# TouScruino-ui2_IL-v0.net
KiCad netlist of a schematic drawn in EAGLE
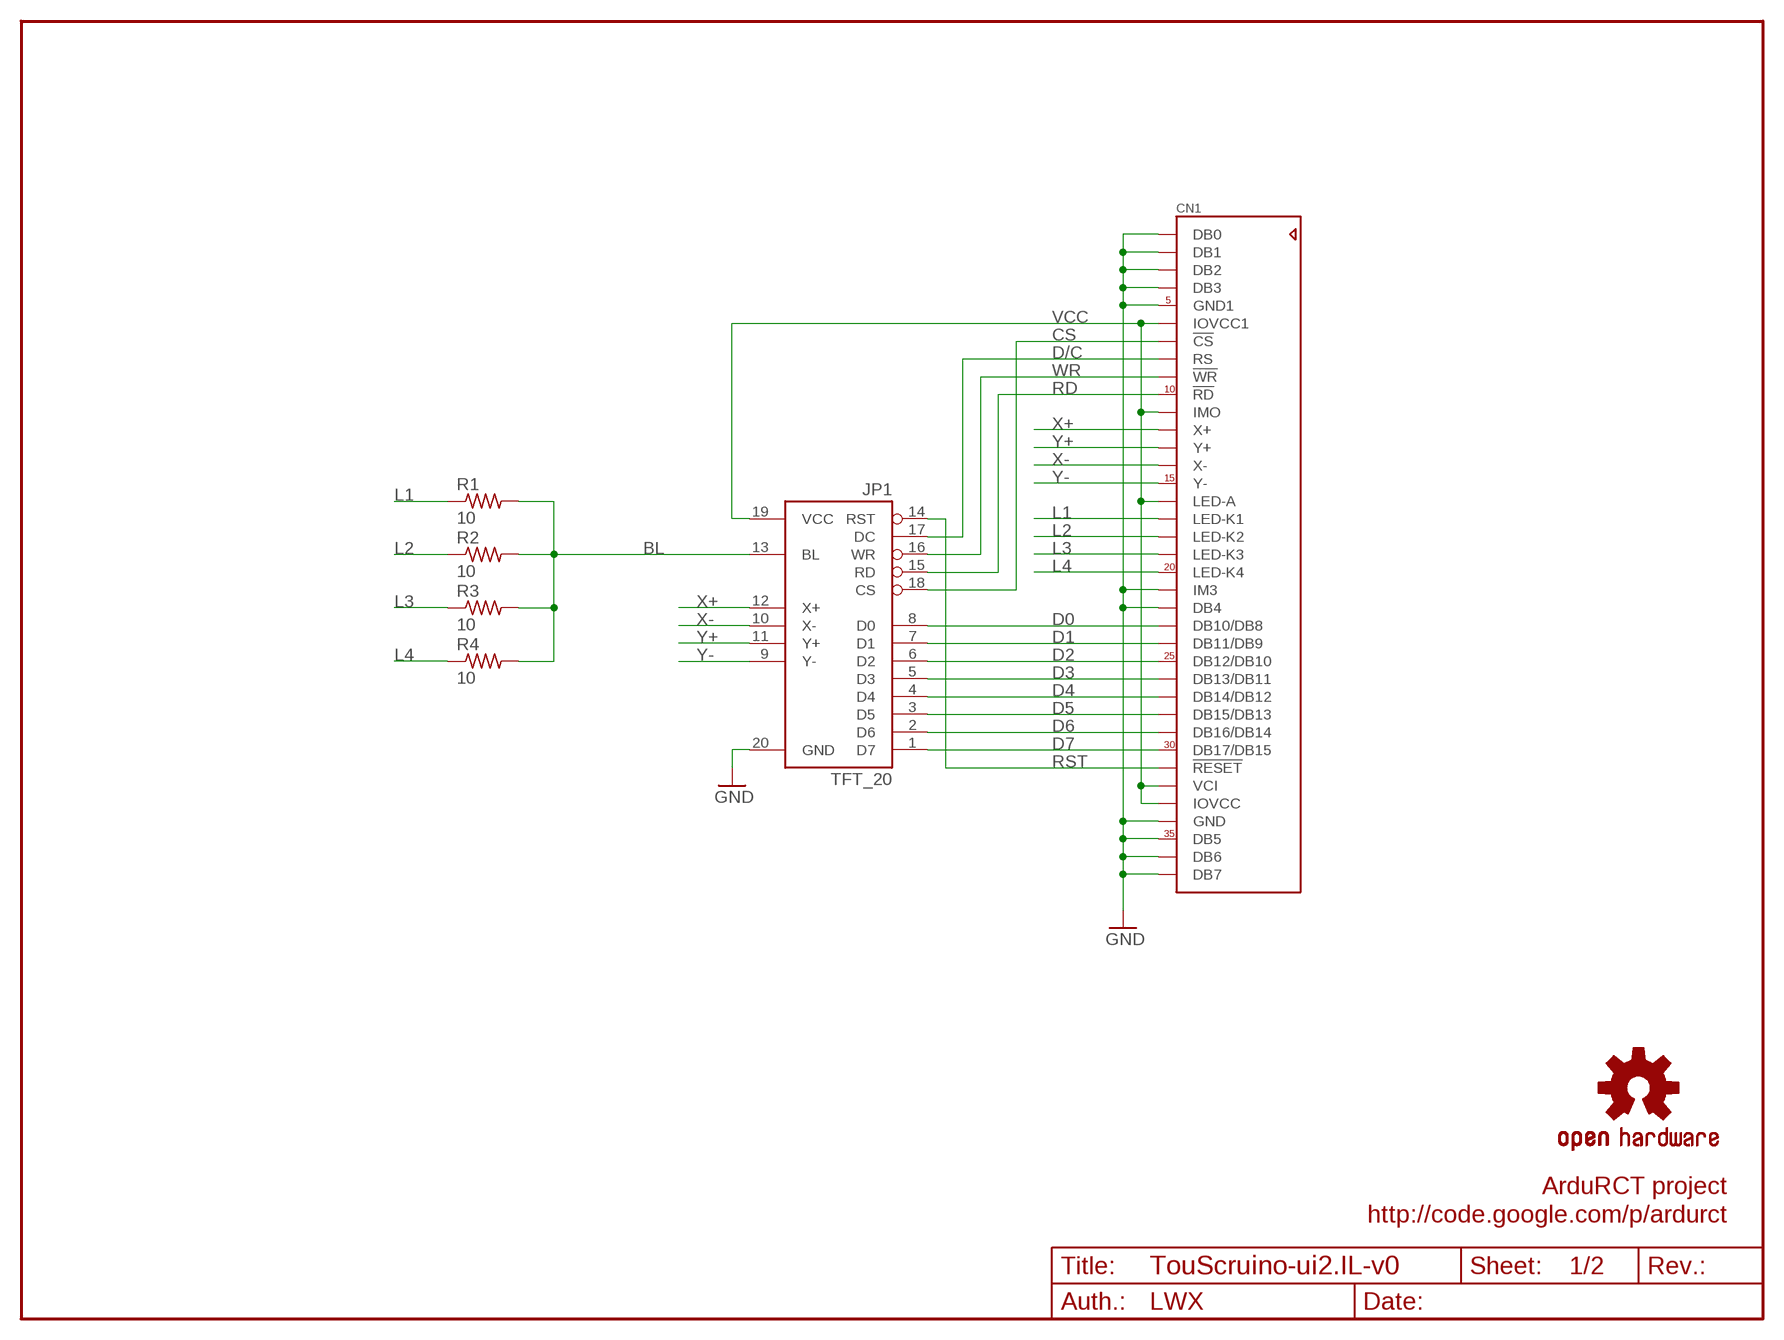
[diagram p0: schematic, sheet 1]

(export (version "E")
  (design (tool "Eeschema 10.0.6"))
  (components
    (comp (ref "CN1")
      (value "ILI9325_LCD1.0MM")
      (footprint "eagle-import:ILI9325_28INCH_TS")
      (libsource (lib "eagle-import") (part "ILI9325_LCD1.0MM"))
    )
    (comp (ref "JP1")
      (value "TFT_20")
      (footprint "eagle-import:TFT_20")
      (libsource (lib "eagle-import") (part "TFT_20"))
    )
    (comp (ref "R1")
      (value "10")
      (footprint "eagle-import:R0603")
      (libsource (lib "eagle-import") (part "R-US_R0603"))
    )
    (comp (ref "R2")
      (value "10")
      (footprint "eagle-import:R0603")
      (libsource (lib "eagle-import") (part "R-US_R0603"))
    )
    (comp (ref "R3")
      (value "10")
      (footprint "eagle-import:R0603")
      (libsource (lib "eagle-import") (part "R-US_R0603"))
    )
    (comp (ref "R4")
      (value "10")
      (footprint "eagle-import:R0603")
      (libsource (lib "eagle-import") (part "R-US_R0603"))
    )
    (comp (ref "U$3")
      (value "OSHW-LOGOM")
      (footprint "eagle-import:OSHW-LOGO-M")
      (libsource (lib "eagle-import") (part "OSHW-LOGOM"))
    )
  )
  (nets
    (net (code "1") (name "/BL") (class "Default")
      (node (ref "JP1") (pin "13") (pinfunction "BL_13") (pintype "bidirectional"))
      (node (ref "R1") (pin "2") (pinfunction "2_2") (pintype "passive"))
      (node (ref "R2") (pin "2") (pinfunction "2_2") (pintype "passive"))
      (node (ref "R3") (pin "2") (pinfunction "2_2") (pintype "passive"))
      (node (ref "R4") (pin "2") (pinfunction "2_2") (pintype "passive"))
    )
    (net (code "2") (name "/CS") (class "Default")
      (node (ref "CN1") (pin "7") (pinfunction "~{CS}_7") (pintype "passive"))
      (node (ref "JP1") (pin "18") (pinfunction "CS_18") (pintype "bidirectional"))
    )
    (net (code "3") (name "/D0") (class "Default")
      (node (ref "CN1") (pin "23") (pinfunction "DB10/DB8_23") (pintype "passive"))
      (node (ref "JP1") (pin "8") (pinfunction "D0_8") (pintype "bidirectional"))
    )
    (net (code "4") (name "/D1") (class "Default")
      (node (ref "CN1") (pin "24") (pinfunction "DB11/DB9_24") (pintype "passive"))
      (node (ref "JP1") (pin "7") (pinfunction "D1_7") (pintype "bidirectional"))
    )
    (net (code "5") (name "/D2") (class "Default")
      (node (ref "CN1") (pin "25") (pinfunction "DB12/DB10_25") (pintype "passive"))
      (node (ref "JP1") (pin "6") (pinfunction "D2_6") (pintype "bidirectional"))
    )
    (net (code "6") (name "/D3") (class "Default")
      (node (ref "CN1") (pin "26") (pinfunction "DB13/DB11_26") (pintype "passive"))
      (node (ref "JP1") (pin "5") (pinfunction "D3_5") (pintype "bidirectional"))
    )
    (net (code "7") (name "/D4") (class "Default")
      (node (ref "CN1") (pin "27") (pinfunction "DB14/DB12_27") (pintype "passive"))
      (node (ref "JP1") (pin "4") (pinfunction "D4_4") (pintype "bidirectional"))
    )
    (net (code "8") (name "/D5") (class "Default")
      (node (ref "CN1") (pin "28") (pinfunction "DB15/DB13_28") (pintype "passive"))
      (node (ref "JP1") (pin "3") (pinfunction "D5_3") (pintype "bidirectional"))
    )
    (net (code "9") (name "/D6") (class "Default")
      (node (ref "CN1") (pin "29") (pinfunction "DB16/DB14_29") (pintype "passive"))
      (node (ref "JP1") (pin "2") (pinfunction "D6_2") (pintype "bidirectional"))
    )
    (net (code "10") (name "/D7") (class "Default")
      (node (ref "CN1") (pin "30") (pinfunction "DB17/DB15_30") (pintype "passive"))
      (node (ref "JP1") (pin "1") (pinfunction "D7_1") (pintype "bidirectional"))
    )
    (net (code "11") (name "/D{slash}C") (class "Default")
      (node (ref "CN1") (pin "8") (pinfunction "RS_8") (pintype "passive"))
      (node (ref "JP1") (pin "17") (pinfunction "DC_17") (pintype "bidirectional"))
    )
    (net (code "12") (name "/L1") (class "Default")
      (node (ref "CN1") (pin "17") (pinfunction "LED-K1_17") (pintype "passive"))
      (node (ref "R1") (pin "1") (pinfunction "1_1") (pintype "passive"))
    )
    (net (code "13") (name "/L2") (class "Default")
      (node (ref "CN1") (pin "18") (pinfunction "LED-K2_18") (pintype "passive"))
      (node (ref "R2") (pin "1") (pinfunction "1_1") (pintype "passive"))
    )
    (net (code "14") (name "/L3") (class "Default")
      (node (ref "CN1") (pin "19") (pinfunction "LED-K3_19") (pintype "passive"))
      (node (ref "R3") (pin "1") (pinfunction "1_1") (pintype "passive"))
    )
    (net (code "15") (name "/L4") (class "Default")
      (node (ref "CN1") (pin "20") (pinfunction "LED-K4_20") (pintype "passive"))
      (node (ref "R4") (pin "1") (pinfunction "1_1") (pintype "passive"))
    )
    (net (code "16") (name "/RD") (class "Default")
      (node (ref "CN1") (pin "10") (pinfunction "~{RD}_10") (pintype "passive"))
      (node (ref "JP1") (pin "15") (pinfunction "RD_15") (pintype "bidirectional"))
    )
    (net (code "17") (name "/RST") (class "Default")
      (node (ref "CN1") (pin "31") (pinfunction "~{RESET}_31") (pintype "passive"))
      (node (ref "JP1") (pin "14") (pinfunction "RST_14") (pintype "bidirectional"))
    )
    (net (code "18") (name "/VCC") (class "Default")
      (node (ref "CN1") (pin "11") (pinfunction "IMO_11") (pintype "passive"))
      (node (ref "CN1") (pin "16") (pinfunction "LED-A_16") (pintype "passive"))
      (node (ref "CN1") (pin "32") (pinfunction "VCI_32") (pintype "power_in"))
      (node (ref "CN1") (pin "33") (pinfunction "IOVCC_33") (pintype "power_in"))
      (node (ref "CN1") (pin "6") (pinfunction "IOVCC1_6") (pintype "power_in"))
      (node (ref "JP1") (pin "19") (pinfunction "VCC_19") (pintype "bidirectional"))
    )
    (net (code "19") (name "/WR") (class "Default")
      (node (ref "CN1") (pin "9") (pinfunction "~{WR}_9") (pintype "passive"))
      (node (ref "JP1") (pin "16") (pinfunction "WR_16") (pintype "bidirectional"))
    )
    (net (code "20") (name "/X+") (class "Default")
      (node (ref "CN1") (pin "12") (pinfunction "X+_12") (pintype "passive"))
      (node (ref "JP1") (pin "12") (pinfunction "X+_12") (pintype "bidirectional"))
    )
    (net (code "21") (name "/X-") (class "Default")
      (node (ref "CN1") (pin "14") (pinfunction "X-_14") (pintype "passive"))
      (node (ref "JP1") (pin "10") (pinfunction "X-_10") (pintype "bidirectional"))
    )
    (net (code "22") (name "/Y+") (class "Default")
      (node (ref "CN1") (pin "13") (pinfunction "Y+_13") (pintype "passive"))
      (node (ref "JP1") (pin "11") (pinfunction "Y+_11") (pintype "bidirectional"))
    )
    (net (code "23") (name "/Y-") (class "Default")
      (node (ref "CN1") (pin "15") (pinfunction "Y-_15") (pintype "passive"))
      (node (ref "JP1") (pin "9") (pinfunction "Y-_9") (pintype "bidirectional"))
    )
    (net (code "24") (name "GND") (class "Default")
      (node (ref "CN1") (pin "1") (pinfunction "DB0_1") (pintype "passive"))
      (node (ref "CN1") (pin "2") (pinfunction "DB1_2") (pintype "passive"))
      (node (ref "CN1") (pin "21") (pinfunction "IM3_21") (pintype "passive"))
      (node (ref "CN1") (pin "22") (pinfunction "DB4_22") (pintype "passive"))
      (node (ref "CN1") (pin "3") (pinfunction "DB2_3") (pintype "passive"))
      (node (ref "CN1") (pin "34") (pinfunction "GND_34") (pintype "power_in"))
      (node (ref "CN1") (pin "35") (pinfunction "DB5_35") (pintype "passive"))
      (node (ref "CN1") (pin "36") (pinfunction "DB6_36") (pintype "passive"))
      (node (ref "CN1") (pin "37") (pinfunction "DB7_37") (pintype "passive"))
      (node (ref "CN1") (pin "4") (pinfunction "DB3_4") (pintype "passive"))
      (node (ref "CN1") (pin "5") (pinfunction "GND1_5") (pintype "power_in"))
      (node (ref "JP1") (pin "20") (pinfunction "GND_20") (pintype "bidirectional"))
    )
  )
)
